# transmiter.net
KiCad netlist of a schematic drawn in EAGLE
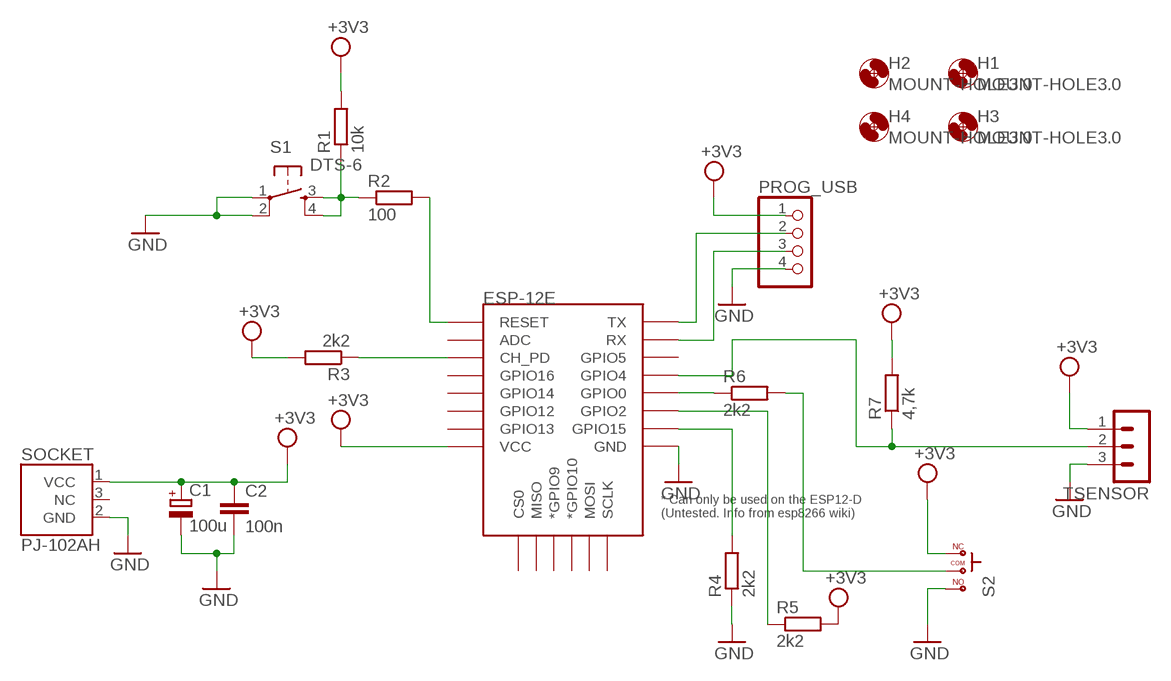
[diagram p0: schematic, sheet 1]

(export (version "E")
  (design (tool "Eeschema 10.0.6"))
  (components
    (comp (ref "C1")
      (value "100u")
      (footprint "eagle-import:E2,5-6")
      (libsource (lib "eagle-import") (part "CPOL-EUE2.5-6"))
    )
    (comp (ref "C2")
      (value "100n")
      (footprint "eagle-import:C025-025X050")
      (libsource (lib "eagle-import") (part "C-EU025-025X050"))
    )
    (comp (ref "ESP-12E")
      (value "ESP12ESMD")
      (footprint "eagle-import:ESP12E-SMD")
      (libsource (lib "eagle-import") (part "ESP12ESMD"))
    )
    (comp (ref "H1")
      (value "MOUNT-HOLE3.0")
      (footprint "eagle-import:3,0")
      (libsource (lib "eagle-import") (part "MOUNT-HOLE3.0"))
    )
    (comp (ref "H2")
      (value "MOUNT-HOLE3.0")
      (footprint "eagle-import:3,0")
      (libsource (lib "eagle-import") (part "MOUNT-HOLE3.0"))
    )
    (comp (ref "H3")
      (value "MOUNT-HOLE3.0")
      (footprint "eagle-import:3,0")
      (libsource (lib "eagle-import") (part "MOUNT-HOLE3.0"))
    )
    (comp (ref "H4")
      (value "MOUNT-HOLE3.0")
      (footprint "eagle-import:3,0")
      (libsource (lib "eagle-import") (part "MOUNT-HOLE3.0"))
    )
    (comp (ref "PROG_USB")
      (value "PINHD-1X4")
      (footprint "eagle-import:1X04")
      (libsource (lib "eagle-import") (part "PINHD-1X4"))
    )
    (comp (ref "R1")
      (value "10k")
      (footprint "eagle-import:0204_7")
      (libsource (lib "eagle-import") (part "R-EU_0204/7"))
    )
    (comp (ref "R2")
      (value "100")
      (footprint "eagle-import:0204_7")
      (libsource (lib "eagle-import") (part "R-EU_0204/7"))
    )
    (comp (ref "R3")
      (value "2k2")
      (footprint "eagle-import:0204_7")
      (libsource (lib "eagle-import") (part "R-EU_0204/7"))
    )
    (comp (ref "R4")
      (value "2k2")
      (footprint "eagle-import:0204_7")
      (libsource (lib "eagle-import") (part "R-EU_0204/7"))
    )
    (comp (ref "R5")
      (value "2k2")
      (footprint "eagle-import:0204_7")
      (libsource (lib "eagle-import") (part "R-EU_0204/7"))
    )
    (comp (ref "R6")
      (value "2k2")
      (footprint "eagle-import:0204_7")
      (libsource (lib "eagle-import") (part "R-EU_0204/7"))
    )
    (comp (ref "R7")
      (value "4,7k")
      (footprint "eagle-import:0204_7")
      (libsource (lib "eagle-import") (part "R-EU_0204/7"))
    )
    (comp (ref "S1")
      (value "DTS-6")
      (footprint "eagle-import:DTS-6")
      (libsource (lib "eagle-import") (part "DTS-6"))
    )
    (comp (ref "S2")
      (value "-SWITCH")
      (footprint "eagle-import:CON3")
      (libsource (lib "eagle-import") (part "-SWITCH"))
    )
    (comp (ref "SOCKET")
      (value "PJ-102AH")
      (footprint "eagle-import:PJ-102AH")
      (libsource (lib "eagle-import") (part "PJ-102AH"))
    )
    (comp (ref "TSENSOR")
      (value "MA03-1")
      (footprint "eagle-import:MA03-1")
      (libsource (lib "eagle-import") (part "MA03-1"))
    )
  )
  (nets
    (net (code "1") (name "+3V3") (class "Default")
      (node (ref "C1") (pin "+") (pinfunction "+_+") (pintype "passive"))
      (node (ref "C2") (pin "1") (pinfunction "1_1") (pintype "passive"))
      (node (ref "ESP-12E") (pin "VCC") (pinfunction "VCC_VCC") (pintype "bidirectional"))
      (node (ref "PROG_USB") (pin "1") (pinfunction "1_1") (pintype "passive"))
      (node (ref "R1") (pin "2") (pinfunction "2_2") (pintype "passive"))
      (node (ref "R3") (pin "2") (pinfunction "2_2") (pintype "passive"))
      (node (ref "R5") (pin "2") (pinfunction "2_2") (pintype "passive"))
      (node (ref "R7") (pin "2") (pinfunction "2_2") (pintype "passive"))
      (node (ref "S2") (pin "P$1") (pinfunction "1_P$1") (pintype "passive"))
      (node (ref "SOCKET") (pin "1") (pinfunction "VCC_1") (pintype "bidirectional"))
      (node (ref "TSENSOR") (pin "1") (pinfunction "1_1") (pintype "passive"))
    )
    (net (code "2") (name "GND") (class "Default")
      (node (ref "C1") (pin "-") (pinfunction "-_-") (pintype "passive"))
      (node (ref "C2") (pin "2") (pinfunction "2_2") (pintype "passive"))
      (node (ref "ESP-12E") (pin "GND") (pinfunction "GND_GND") (pintype "bidirectional"))
      (node (ref "PROG_USB") (pin "4") (pinfunction "4_4") (pintype "passive"))
      (node (ref "R4") (pin "1") (pinfunction "1_1") (pintype "passive"))
      (node (ref "S1") (pin "1") (pinfunction "1_1") (pintype "passive"))
      (node (ref "S1") (pin "2") (pinfunction "2_2") (pintype "passive"))
      (node (ref "S2") (pin "P$3") (pinfunction "3_P$3") (pintype "passive"))
      (node (ref "SOCKET") (pin "2") (pinfunction "GND_2") (pintype "bidirectional"))
      (node (ref "TSENSOR") (pin "3") (pinfunction "3_3") (pintype "passive"))
    )
    (net (code "3") (name "Net-(ESP-12E-PadCH_PD)") (class "Default")
      (node (ref "ESP-12E") (pin "CH_PD") (pinfunction "CH_PD_CH_PD") (pintype "bidirectional"))
      (node (ref "R3") (pin "1") (pinfunction "1_1") (pintype "passive"))
    )
    (net (code "4") (name "Net-(ESP-12E-PadGPIO0)") (class "Default")
      (node (ref "ESP-12E") (pin "GPIO0") (pinfunction "GPIO0_GPIO0") (pintype "bidirectional"))
      (node (ref "R6") (pin "1") (pinfunction "1_1") (pintype "passive"))
    )
    (net (code "5") (name "Net-(ESP-12E-PadGPIO2)") (class "Default")
      (node (ref "ESP-12E") (pin "GPIO2") (pinfunction "GPIO2_GPIO2") (pintype "bidirectional"))
      (node (ref "R5") (pin "1") (pinfunction "1_1") (pintype "passive"))
    )
    (net (code "6") (name "Net-(ESP-12E-PadGPIO4)") (class "Default")
      (node (ref "ESP-12E") (pin "GPIO4") (pinfunction "GPIO4_GPIO4") (pintype "bidirectional"))
      (node (ref "R7") (pin "1") (pinfunction "1_1") (pintype "passive"))
      (node (ref "TSENSOR") (pin "2") (pinfunction "2_2") (pintype "passive"))
    )
    (net (code "7") (name "Net-(ESP-12E-PadGPIO15)") (class "Default")
      (node (ref "ESP-12E") (pin "GPIO15") (pinfunction "GPIO15_GPIO15") (pintype "bidirectional"))
      (node (ref "R4") (pin "2") (pinfunction "2_2") (pintype "passive"))
    )
    (net (code "8") (name "Net-(ESP-12E-PadRESET)") (class "Default")
      (node (ref "ESP-12E") (pin "RESET") (pinfunction "RESET_RESET") (pintype "bidirectional"))
      (node (ref "R2") (pin "2") (pinfunction "2_2") (pintype "passive"))
    )
    (net (code "9") (name "Net-(ESP-12E-RX)") (class "Default")
      (node (ref "ESP-12E") (pin "RXD0") (pinfunction "RX_RXD0") (pintype "bidirectional"))
      (node (ref "PROG_USB") (pin "3") (pinfunction "3_3") (pintype "passive"))
    )
    (net (code "10") (name "Net-(ESP-12E-TX)") (class "Default")
      (node (ref "ESP-12E") (pin "TXD0") (pinfunction "TX_TXD0") (pintype "bidirectional"))
      (node (ref "PROG_USB") (pin "2") (pinfunction "2_2") (pintype "passive"))
    )
    (net (code "11") (name "Net-(R1-Pad1)") (class "Default")
      (node (ref "R1") (pin "1") (pinfunction "1_1") (pintype "passive"))
      (node (ref "R2") (pin "1") (pinfunction "1_1") (pintype "passive"))
      (node (ref "S1") (pin "3") (pinfunction "3_3") (pintype "passive"))
      (node (ref "S1") (pin "4") (pinfunction "4_4") (pintype "passive"))
    )
    (net (code "12") (name "Net-(S2-2)") (class "Default")
      (node (ref "R6") (pin "2") (pinfunction "2_2") (pintype "passive"))
      (node (ref "S2") (pin "P$2") (pinfunction "2_P$2") (pintype "passive"))
    )
    (net (code "13") (name "unconnected-(ESP-12E-*GPIO9-PadGPIO9)") (class "Default")
      (node (ref "ESP-12E") (pin "GPIO9") (pinfunction "*GPIO9_GPIO9") (pintype "bidirectional"))
    )
    (net (code "14") (name "unconnected-(ESP-12E-*GPIO10-PadGPIO10)") (class "Default")
      (node (ref "ESP-12E") (pin "GPIO10") (pinfunction "*GPIO10_GPIO10") (pintype "bidirectional"))
    )
    (net (code "15") (name "unconnected-(ESP-12E-PadADC)") (class "Default")
      (node (ref "ESP-12E") (pin "ADC") (pinfunction "ADC_ADC") (pintype "bidirectional"))
    )
    (net (code "16") (name "unconnected-(ESP-12E-PadCS0)") (class "Default")
      (node (ref "ESP-12E") (pin "CS0") (pinfunction "CS0_CS0") (pintype "bidirectional"))
    )
    (net (code "17") (name "unconnected-(ESP-12E-PadGPIO5)") (class "Default")
      (node (ref "ESP-12E") (pin "GPIO5") (pinfunction "GPIO5_GPIO5") (pintype "bidirectional"))
    )
    (net (code "18") (name "unconnected-(ESP-12E-PadGPIO12)") (class "Default")
      (node (ref "ESP-12E") (pin "GPIO12") (pinfunction "GPIO12_GPIO12") (pintype "bidirectional"))
    )
    (net (code "19") (name "unconnected-(ESP-12E-PadGPIO13)") (class "Default")
      (node (ref "ESP-12E") (pin "GPIO13") (pinfunction "GPIO13_GPIO13") (pintype "bidirectional"))
    )
    (net (code "20") (name "unconnected-(ESP-12E-PadGPIO14)") (class "Default")
      (node (ref "ESP-12E") (pin "GPIO14") (pinfunction "GPIO14_GPIO14") (pintype "bidirectional"))
    )
    (net (code "21") (name "unconnected-(ESP-12E-PadGPIO16)") (class "Default")
      (node (ref "ESP-12E") (pin "GPIO16") (pinfunction "GPIO16_GPIO16") (pintype "bidirectional"))
    )
    (net (code "22") (name "unconnected-(ESP-12E-PadMISO)") (class "Default")
      (node (ref "ESP-12E") (pin "MISO") (pinfunction "MISO_MISO") (pintype "bidirectional"))
    )
    (net (code "23") (name "unconnected-(ESP-12E-PadMOSI)") (class "Default")
      (node (ref "ESP-12E") (pin "MOSI") (pinfunction "MOSI_MOSI") (pintype "bidirectional"))
    )
    (net (code "24") (name "unconnected-(ESP-12E-PadSCLK)") (class "Default")
      (node (ref "ESP-12E") (pin "SCLK") (pinfunction "SCLK_SCLK") (pintype "bidirectional"))
    )
    (net (code "25") (name "unconnected-(SOCKET-NC-Pad3)") (class "Default")
      (node (ref "SOCKET") (pin "3") (pinfunction "NC_3") (pintype "bidirectional"))
    )
  )
)
